# power_board.net
KiCad netlist of a schematic drawn in EAGLE
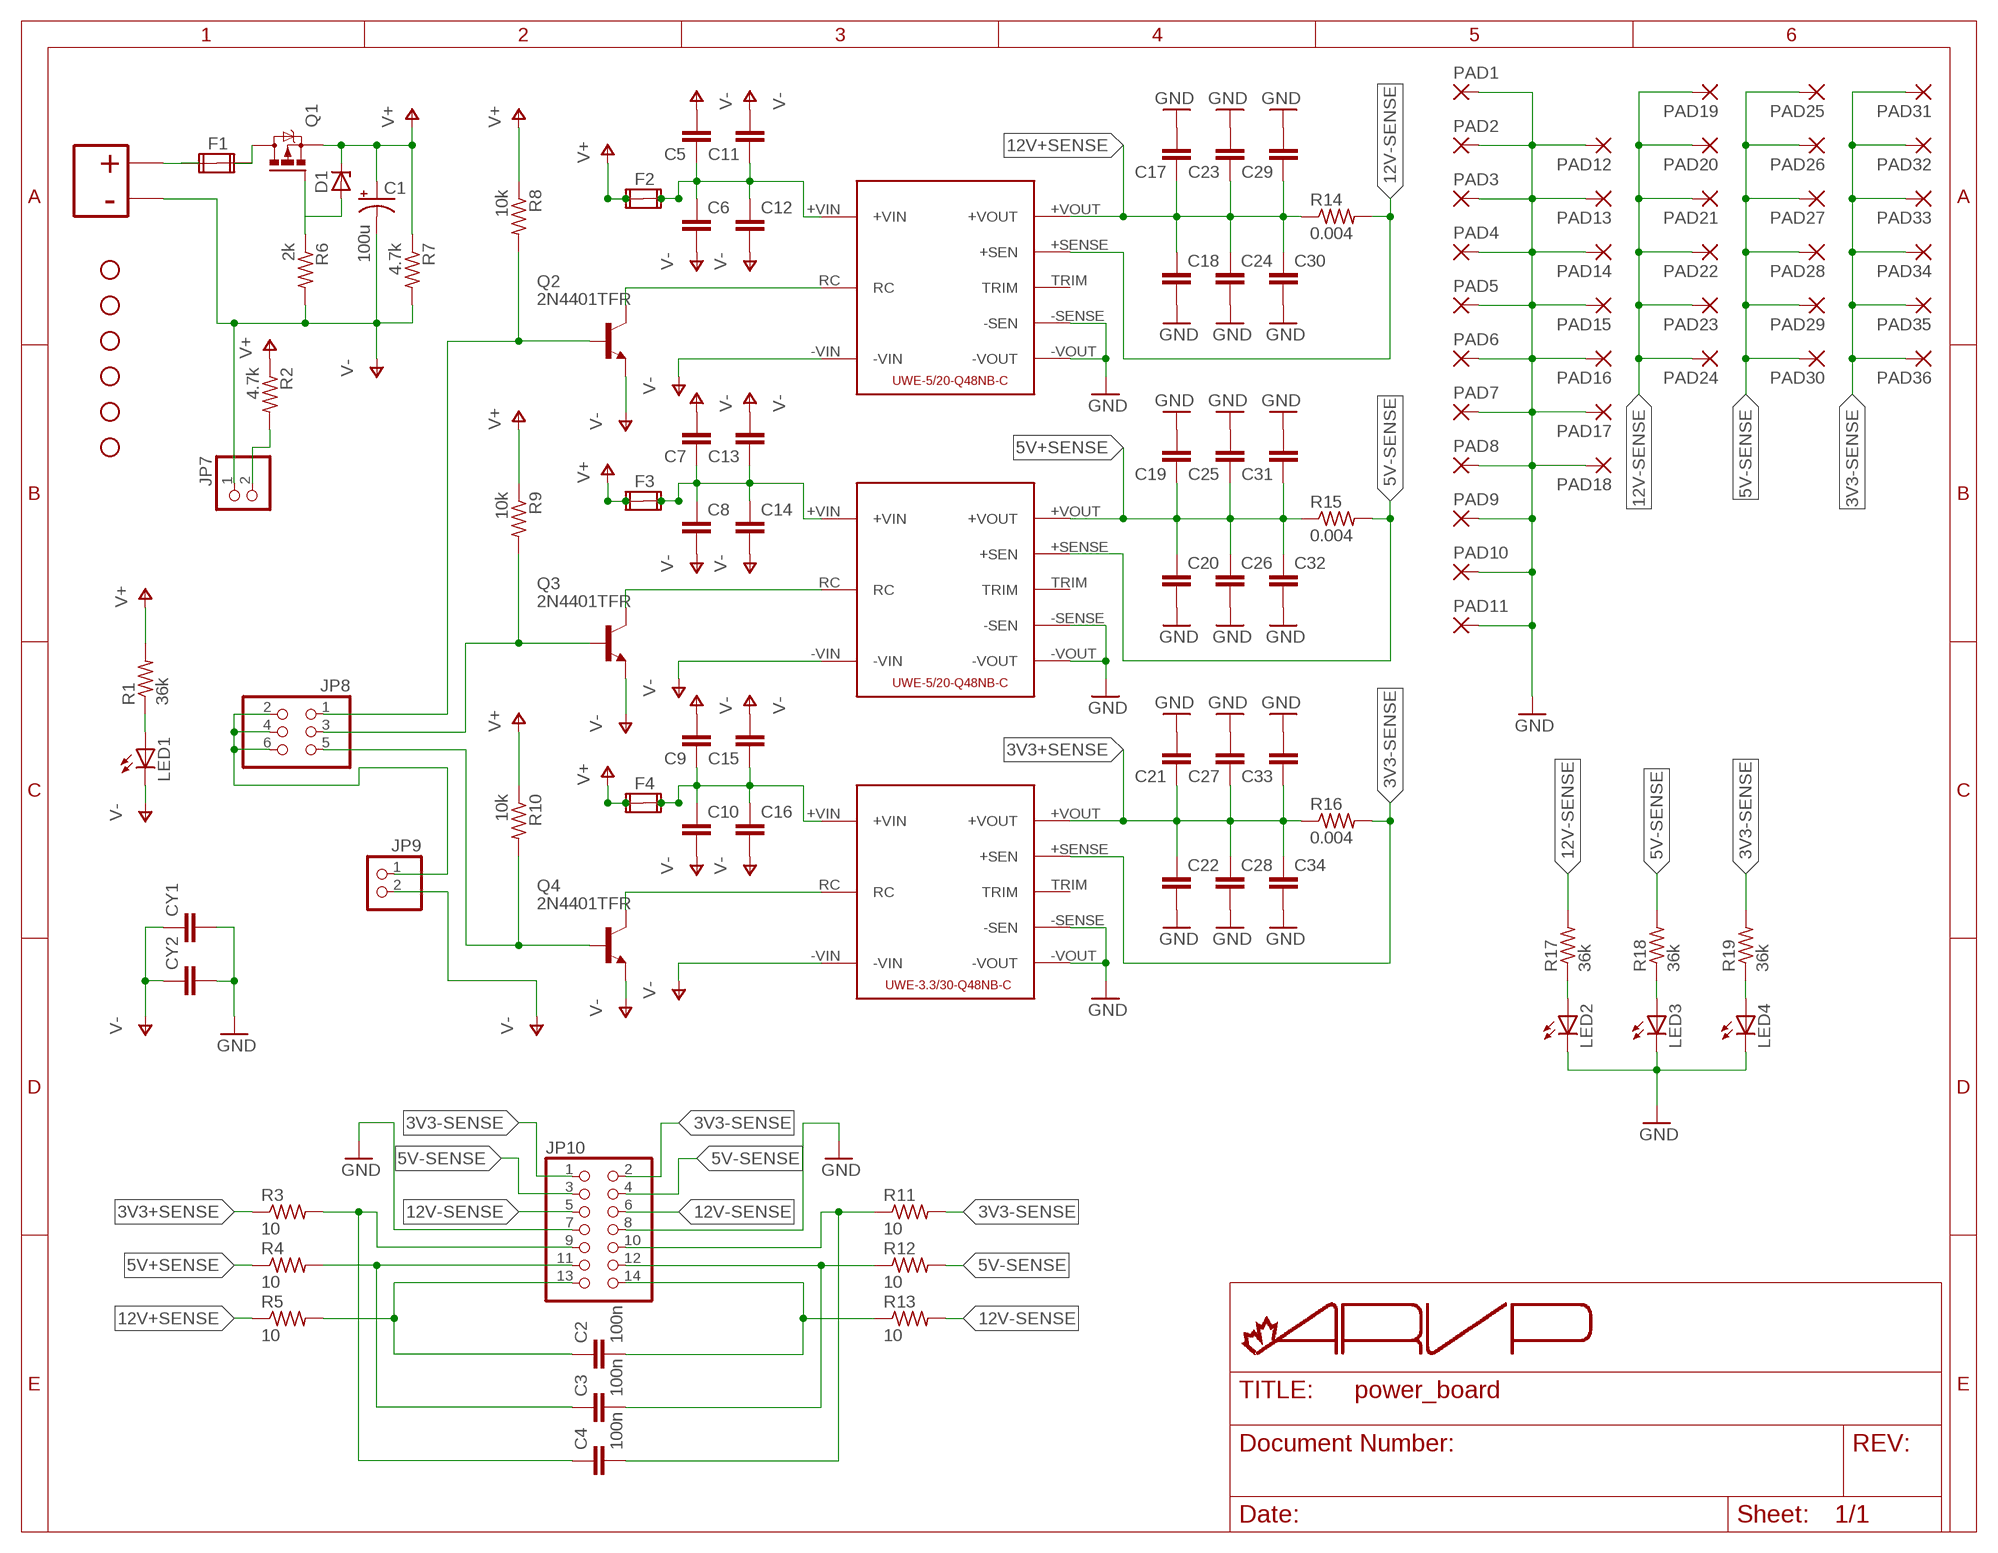
[diagram p0: schematic, sheet 1]

(export (version "E")
  (design (tool "Eeschema 10.0.6"))
  (components
    (comp (ref "C1")
      (value "100u")
      (footprint "eagle-import:E3,5-8")
      (libsource (lib "eagle-import") (part "CPOL-USE3.5-8"))
    )
    (comp (ref "C2")
      (value "100n")
      (footprint "eagle-import:C025-024X044")
      (libsource (lib "eagle-import") (part "C-EU025-024X044"))
    )
    (comp (ref "C3")
      (value "100n")
      (footprint "eagle-import:C025-024X044")
      (libsource (lib "eagle-import") (part "C-EU025-024X044"))
    )
    (comp (ref "C4")
      (value "100n")
      (footprint "eagle-import:C025-024X044")
      (libsource (lib "eagle-import") (part "C-EU025-024X044"))
    )
    (comp (ref "C5")
      (value "C-EU050-035X075")
      (footprint "eagle-import:C050-035X075")
      (libsource (lib "eagle-import") (part "C-EU050-035X075"))
    )
    (comp (ref "C6")
      (value "C-EU050-035X075")
      (footprint "eagle-import:C050-035X075")
      (libsource (lib "eagle-import") (part "C-EU050-035X075"))
    )
    (comp (ref "C7")
      (value "C-EU050-035X075")
      (footprint "eagle-import:C050-035X075")
      (libsource (lib "eagle-import") (part "C-EU050-035X075"))
    )
    (comp (ref "C8")
      (value "C-EU050-035X075")
      (footprint "eagle-import:C050-035X075")
      (libsource (lib "eagle-import") (part "C-EU050-035X075"))
    )
    (comp (ref "C9")
      (value "C-EU050-035X075")
      (footprint "eagle-import:C050-035X075")
      (libsource (lib "eagle-import") (part "C-EU050-035X075"))
    )
    (comp (ref "C10")
      (value "C-EU050-035X075")
      (footprint "eagle-import:C050-035X075")
      (libsource (lib "eagle-import") (part "C-EU050-035X075"))
    )
    (comp (ref "C11")
      (value "C-EU050-035X075")
      (footprint "eagle-import:C050-035X075")
      (libsource (lib "eagle-import") (part "C-EU050-035X075"))
    )
    (comp (ref "C12")
      (value "C-EU050-035X075")
      (footprint "eagle-import:C050-035X075")
      (libsource (lib "eagle-import") (part "C-EU050-035X075"))
    )
    (comp (ref "C13")
      (value "C-EU050-035X075")
      (footprint "eagle-import:C050-035X075")
      (libsource (lib "eagle-import") (part "C-EU050-035X075"))
    )
    (comp (ref "C14")
      (value "C-EU050-035X075")
      (footprint "eagle-import:C050-035X075")
      (libsource (lib "eagle-import") (part "C-EU050-035X075"))
    )
    (comp (ref "C15")
      (value "C-EU050-035X075")
      (footprint "eagle-import:C050-035X075")
      (libsource (lib "eagle-import") (part "C-EU050-035X075"))
    )
    (comp (ref "C16")
      (value "C-EU050-035X075")
      (footprint "eagle-import:C050-035X075")
      (libsource (lib "eagle-import") (part "C-EU050-035X075"))
    )
    (comp (ref "C17")
      (value "C-EU025-040X050")
      (footprint "eagle-import:C025-040X050")
      (libsource (lib "eagle-import") (part "C-EU025-040X050"))
    )
    (comp (ref "C18")
      (value "C-EU025-040X050")
      (footprint "eagle-import:C025-040X050")
      (libsource (lib "eagle-import") (part "C-EU025-040X050"))
    )
    (comp (ref "C19")
      (value "C-EU025-040X050")
      (footprint "eagle-import:C025-040X050")
      (libsource (lib "eagle-import") (part "C-EU025-040X050"))
    )
    (comp (ref "C20")
      (value "C-EU025-040X050")
      (footprint "eagle-import:C025-040X050")
      (libsource (lib "eagle-import") (part "C-EU025-040X050"))
    )
    (comp (ref "C21")
      (value "C-EU025-040X050")
      (footprint "eagle-import:C025-040X050")
      (libsource (lib "eagle-import") (part "C-EU025-040X050"))
    )
    (comp (ref "C22")
      (value "C-EU025-040X050")
      (footprint "eagle-import:C025-040X050")
      (libsource (lib "eagle-import") (part "C-EU025-040X050"))
    )
    (comp (ref "C23")
      (value "C-EU025-040X050")
      (footprint "eagle-import:C025-040X050")
      (libsource (lib "eagle-import") (part "C-EU025-040X050"))
    )
    (comp (ref "C24")
      (value "C-EU025-040X050")
      (footprint "eagle-import:C025-040X050")
      (libsource (lib "eagle-import") (part "C-EU025-040X050"))
    )
    (comp (ref "C25")
      (value "C-EU025-040X050")
      (footprint "eagle-import:C025-040X050")
      (libsource (lib "eagle-import") (part "C-EU025-040X050"))
    )
    (comp (ref "C26")
      (value "C-EU025-040X050")
      (footprint "eagle-import:C025-040X050")
      (libsource (lib "eagle-import") (part "C-EU025-040X050"))
    )
    (comp (ref "C27")
      (value "C-EU025-040X050")
      (footprint "eagle-import:C025-040X050")
      (libsource (lib "eagle-import") (part "C-EU025-040X050"))
    )
    (comp (ref "C28")
      (value "C-EU025-040X050")
      (footprint "eagle-import:C025-040X050")
      (libsource (lib "eagle-import") (part "C-EU025-040X050"))
    )
    (comp (ref "C29")
      (value "C-EU025-040X050")
      (footprint "eagle-import:C025-040X050")
      (libsource (lib "eagle-import") (part "C-EU025-040X050"))
    )
    (comp (ref "C30")
      (value "C-EU025-040X050")
      (footprint "eagle-import:C025-040X050")
      (libsource (lib "eagle-import") (part "C-EU025-040X050"))
    )
    (comp (ref "C31")
      (value "C-EU025-040X050")
      (footprint "eagle-import:C025-040X050")
      (libsource (lib "eagle-import") (part "C-EU025-040X050"))
    )
    (comp (ref "C32")
      (value "C-EU025-040X050")
      (footprint "eagle-import:C025-040X050")
      (libsource (lib "eagle-import") (part "C-EU025-040X050"))
    )
    (comp (ref "C33")
      (value "C-EU025-040X050")
      (footprint "eagle-import:C025-040X050")
      (libsource (lib "eagle-import") (part "C-EU025-040X050"))
    )
    (comp (ref "C34")
      (value "C-EU025-040X050")
      (footprint "eagle-import:C025-040X050")
      (libsource (lib "eagle-import") (part "C-EU025-040X050"))
    )
    (comp (ref "CY1")
      (value "CYYC7B5")
      (footprint "eagle-import:YC7B5")
      (libsource (lib "eagle-import") (part "CYYC7B5"))
    )
    (comp (ref "CY2")
      (value "CYYC7B5")
      (footprint "eagle-import:YC7B5")
      (libsource (lib "eagle-import") (part "CYYC7B5"))
    )
    (comp (ref "D1")
      (value "BZV10")
      (footprint "eagle-import:DO34Z7")
      (libsource (lib "eagle-import") (part "BZV10"))
    )
    (comp (ref "F1")
      (value "FUSE2P")
      (footprint "eagle-import:FUSE1")
      (libsource (lib "eagle-import") (part "FUSE2P"))
    )
    (comp (ref "F2")
      (value "FUSE2P")
      (footprint "eagle-import:FUSE1")
      (libsource (lib "eagle-import") (part "FUSE2P"))
    )
    (comp (ref "F3")
      (value "FUSE2P")
      (footprint "eagle-import:FUSE1")
      (libsource (lib "eagle-import") (part "FUSE2P"))
    )
    (comp (ref "F4")
      (value "FUSE2P")
      (footprint "eagle-import:FUSE1")
      (libsource (lib "eagle-import") (part "FUSE2P"))
    )
    (comp (ref "JP1")
      (value "STAND-OFF")
      (footprint "eagle-import:STAND-OFF")
      (libsource (lib "eagle-import") (part "STAND-OFF"))
    )
    (comp (ref "JP2")
      (value "STAND-OFF")
      (footprint "eagle-import:STAND-OFF")
      (libsource (lib "eagle-import") (part "STAND-OFF"))
    )
    (comp (ref "JP3")
      (value "STAND-OFF")
      (footprint "eagle-import:STAND-OFF")
      (libsource (lib "eagle-import") (part "STAND-OFF"))
    )
    (comp (ref "JP4")
      (value "STAND-OFF")
      (footprint "eagle-import:STAND-OFF")
      (libsource (lib "eagle-import") (part "STAND-OFF"))
    )
    (comp (ref "JP5")
      (value "STAND-OFF")
      (footprint "eagle-import:STAND-OFF")
      (libsource (lib "eagle-import") (part "STAND-OFF"))
    )
    (comp (ref "JP6")
      (value "STAND-OFF")
      (footprint "eagle-import:STAND-OFF")
      (libsource (lib "eagle-import") (part "STAND-OFF"))
    )
    (comp (ref "JP7")
      (value "PINHD-1X2/90")
      (footprint "eagle-import:1X02_90")
      (libsource (lib "eagle-import") (part "PINHD-1X2/90"))
    )
    (comp (ref "JP8")
      (value "PINHD-2X3/90")
      (footprint "eagle-import:2X03_90")
      (libsource (lib "eagle-import") (part "PINHD-2X3/90"))
    )
    (comp (ref "JP9")
      (value "PINHD-1X2/90")
      (footprint "eagle-import:1X02_90")
      (libsource (lib "eagle-import") (part "PINHD-1X2/90"))
    )
    (comp (ref "JP10")
      (value "PINHD-2X7")
      (footprint "eagle-import:2X07")
      (libsource (lib "eagle-import") (part "PINHD-2X7"))
    )
    (comp (ref "LED1")
      (value "LED3MM")
      (footprint "eagle-import:LED3MM")
      (libsource (lib "eagle-import") (part "LED3MM"))
    )
    (comp (ref "LED2")
      (value "LED3MM")
      (footprint "eagle-import:LED3MM")
      (libsource (lib "eagle-import") (part "LED3MM"))
    )
    (comp (ref "LED3")
      (value "LED3MM")
      (footprint "eagle-import:LED3MM")
      (libsource (lib "eagle-import") (part "LED3MM"))
    )
    (comp (ref "LED4")
      (value "LED3MM")
      (footprint "eagle-import:LED3MM")
      (libsource (lib "eagle-import") (part "LED3MM"))
    )
    (comp (ref "PAD1")
      (value "WIREPAD3,17/1,3")
      (footprint "eagle-import:3,17_1,3")
      (libsource (lib "eagle-import") (part "WIREPAD3,17/1,3"))
    )
    (comp (ref "PAD2")
      (value "WIREPAD3,17/1,3")
      (footprint "eagle-import:3,17_1,3")
      (libsource (lib "eagle-import") (part "WIREPAD3,17/1,3"))
    )
    (comp (ref "PAD3")
      (value "WIREPAD3,17/1,3")
      (footprint "eagle-import:3,17_1,3")
      (libsource (lib "eagle-import") (part "WIREPAD3,17/1,3"))
    )
    (comp (ref "PAD4")
      (value "WIREPAD3,17/1,3")
      (footprint "eagle-import:3,17_1,3")
      (libsource (lib "eagle-import") (part "WIREPAD3,17/1,3"))
    )
    (comp (ref "PAD5")
      (value "WIREPAD3,17/1,3")
      (footprint "eagle-import:3,17_1,3")
      (libsource (lib "eagle-import") (part "WIREPAD3,17/1,3"))
    )
    (comp (ref "PAD6")
      (value "WIREPAD3,17/1,3")
      (footprint "eagle-import:3,17_1,3")
      (libsource (lib "eagle-import") (part "WIREPAD3,17/1,3"))
    )
    (comp (ref "PAD7")
      (value "WIREPAD3,17/1,3")
      (footprint "eagle-import:3,17_1,3")
      (libsource (lib "eagle-import") (part "WIREPAD3,17/1,3"))
    )
    (comp (ref "PAD8")
      (value "WIREPAD3,17/1,3")
      (footprint "eagle-import:3,17_1,3")
      (libsource (lib "eagle-import") (part "WIREPAD3,17/1,3"))
    )
    (comp (ref "PAD9")
      (value "WIREPAD3,17/1,3")
      (footprint "eagle-import:3,17_1,3")
      (libsource (lib "eagle-import") (part "WIREPAD3,17/1,3"))
    )
    (comp (ref "PAD10")
      (value "WIREPAD3,17/1,3")
      (footprint "eagle-import:3,17_1,3")
      (libsource (lib "eagle-import") (part "WIREPAD3,17/1,3"))
    )
    (comp (ref "PAD11")
      (value "WIREPAD3,17/1,3")
      (footprint "eagle-import:3,17_1,3")
      (libsource (lib "eagle-import") (part "WIREPAD3,17/1,3"))
    )
    (comp (ref "PAD12")
      (value "WIREPAD3,17/1,3")
      (footprint "eagle-import:3,17_1,3")
      (libsource (lib "eagle-import") (part "WIREPAD3,17/1,3"))
    )
    (comp (ref "PAD13")
      (value "WIREPAD3,17/1,3")
      (footprint "eagle-import:3,17_1,3")
      (libsource (lib "eagle-import") (part "WIREPAD3,17/1,3"))
    )
    (comp (ref "PAD14")
      (value "WIREPAD3,17/1,3")
      (footprint "eagle-import:3,17_1,3")
      (libsource (lib "eagle-import") (part "WIREPAD3,17/1,3"))
    )
    (comp (ref "PAD15")
      (value "WIREPAD3,17/1,3")
      (footprint "eagle-import:3,17_1,3")
      (libsource (lib "eagle-import") (part "WIREPAD3,17/1,3"))
    )
    (comp (ref "PAD16")
      (value "WIREPAD3,17/1,3")
      (footprint "eagle-import:3,17_1,3")
      (libsource (lib "eagle-import") (part "WIREPAD3,17/1,3"))
    )
    (comp (ref "PAD17")
      (value "WIREPAD3,17/1,3")
      (footprint "eagle-import:3,17_1,3")
      (libsource (lib "eagle-import") (part "WIREPAD3,17/1,3"))
    )
    (comp (ref "PAD18")
      (value "WIREPAD3,17/1,3")
      (footprint "eagle-import:3,17_1,3")
      (libsource (lib "eagle-import") (part "WIREPAD3,17/1,3"))
    )
    (comp (ref "PAD19")
      (value "WIREPAD3,17/1,3")
      (footprint "eagle-import:3,17_1,3")
      (libsource (lib "eagle-import") (part "WIREPAD3,17/1,3"))
    )
    (comp (ref "PAD20")
      (value "WIREPAD3,17/1,3")
      (footprint "eagle-import:3,17_1,3")
      (libsource (lib "eagle-import") (part "WIREPAD3,17/1,3"))
    )
    (comp (ref "PAD21")
      (value "WIREPAD3,17/1,3")
      (footprint "eagle-import:3,17_1,3")
      (libsource (lib "eagle-import") (part "WIREPAD3,17/1,3"))
    )
    (comp (ref "PAD22")
      (value "WIREPAD3,17/1,3")
      (footprint "eagle-import:3,17_1,3")
      (libsource (lib "eagle-import") (part "WIREPAD3,17/1,3"))
    )
    (comp (ref "PAD23")
      (value "WIREPAD3,17/1,3")
      (footprint "eagle-import:3,17_1,3")
      (libsource (lib "eagle-import") (part "WIREPAD3,17/1,3"))
    )
    (comp (ref "PAD24")
      (value "WIREPAD3,17/1,3")
      (footprint "eagle-import:3,17_1,3")
      (libsource (lib "eagle-import") (part "WIREPAD3,17/1,3"))
    )
    (comp (ref "PAD25")
      (value "WIREPAD3,17/1,3")
      (footprint "eagle-import:3,17_1,3")
      (libsource (lib "eagle-import") (part "WIREPAD3,17/1,3"))
    )
    (comp (ref "PAD26")
      (value "WIREPAD3,17/1,3")
      (footprint "eagle-import:3,17_1,3")
      (libsource (lib "eagle-import") (part "WIREPAD3,17/1,3"))
    )
    (comp (ref "PAD27")
      (value "WIREPAD3,17/1,3")
      (footprint "eagle-import:3,17_1,3")
      (libsource (lib "eagle-import") (part "WIREPAD3,17/1,3"))
    )
    (comp (ref "PAD28")
      (value "WIREPAD3,17/1,3")
      (footprint "eagle-import:3,17_1,3")
      (libsource (lib "eagle-import") (part "WIREPAD3,17/1,3"))
    )
    (comp (ref "PAD29")
      (value "WIREPAD3,17/1,3")
      (footprint "eagle-import:3,17_1,3")
      (libsource (lib "eagle-import") (part "WIREPAD3,17/1,3"))
    )
    (comp (ref "PAD30")
      (value "WIREPAD3,17/1,3")
      (footprint "eagle-import:3,17_1,3")
      (libsource (lib "eagle-import") (part "WIREPAD3,17/1,3"))
    )
    (comp (ref "PAD31")
      (value "WIREPAD3,17/1,3")
      (footprint "eagle-import:3,17_1,3")
      (libsource (lib "eagle-import") (part "WIREPAD3,17/1,3"))
    )
    (comp (ref "PAD32")
      (value "WIREPAD3,17/1,3")
      (footprint "eagle-import:3,17_1,3")
      (libsource (lib "eagle-import") (part "WIREPAD3,17/1,3"))
    )
    (comp (ref "PAD33")
      (value "WIREPAD3,17/1,3")
      (footprint "eagle-import:3,17_1,3")
      (libsource (lib "eagle-import") (part "WIREPAD3,17/1,3"))
    )
    (comp (ref "PAD34")
      (value "WIREPAD3,17/1,3")
      (footprint "eagle-import:3,17_1,3")
      (libsource (lib "eagle-import") (part "WIREPAD3,17/1,3"))
    )
    (comp (ref "PAD35")
      (value "WIREPAD3,17/1,3")
      (footprint "eagle-import:3,17_1,3")
      (libsource (lib "eagle-import") (part "WIREPAD3,17/1,3"))
    )
    (comp (ref "PAD36")
      (value "WIREPAD3,17/1,3")
      (footprint "eagle-import:3,17_1,3")
      (libsource (lib "eagle-import") (part "WIREPAD3,17/1,3"))
    )
    (comp (ref "Q1")
      (value "IPP80P03P4L04AKSA1")
      (footprint "eagle-import:TO220BV")
      (libsource (lib "eagle-import") (part "IPP80P03P4L04AKSA1"))
    )
    (comp (ref "Q2")
      (value "2N4401TFR")
      (footprint "eagle-import:TO92-EBC")
      (libsource (lib "eagle-import") (part "2N4401TFR"))
    )
    (comp (ref "Q3")
      (value "2N4401TFR")
      (footprint "eagle-import:TO92-EBC")
      (libsource (lib "eagle-import") (part "2N4401TFR"))
    )
    (comp (ref "Q4")
      (value "2N4401TFR")
      (footprint "eagle-import:TO92-EBC")
      (libsource (lib "eagle-import") (part "2N4401TFR"))
    )
    (comp (ref "R1")
      (value "36k")
      (footprint "eagle-import:0204_7")
      (libsource (lib "eagle-import") (part "resistor_R-US_0204/7"))
    )
    (comp (ref "R2")
      (value "4.7k")
      (footprint "eagle-import:0204_7")
      (libsource (lib "eagle-import") (part "resistor_R-US_0204/7"))
    )
    (comp (ref "R3")
      (value "10")
      (footprint "eagle-import:0204_5")
      (libsource (lib "eagle-import") (part "R-US_0204/5"))
    )
    (comp (ref "R4")
      (value "10")
      (footprint "eagle-import:0204_5")
      (libsource (lib "eagle-import") (part "R-US_0204/5"))
    )
    (comp (ref "R5")
      (value "10")
      (footprint "eagle-import:0204_5")
      (libsource (lib "eagle-import") (part "R-US_0204/5"))
    )
    (comp (ref "R6")
      (value "2k")
      (footprint "eagle-import:0204_7")
      (libsource (lib "eagle-import") (part "resistor_R-US_0204/7"))
    )
    (comp (ref "R7")
      (value "4.7k")
      (footprint "eagle-import:0204_7")
      (libsource (lib "eagle-import") (part "resistor_R-US_0204/7"))
    )
    (comp (ref "R8")
      (value "10k")
      (footprint "eagle-import:0204_7")
      (libsource (lib "eagle-import") (part "resistor_R-US_0204/7"))
    )
    (comp (ref "R9")
      (value "10k")
      (footprint "eagle-import:0204_7")
      (libsource (lib "eagle-import") (part "resistor_R-US_0204/7"))
    )
    (comp (ref "R10")
      (value "10k")
      (footprint "eagle-import:0204_7")
      (libsource (lib "eagle-import") (part "resistor_R-US_0204/7"))
    )
    (comp (ref "R11")
      (value "10")
      (footprint "eagle-import:0204_5")
      (libsource (lib "eagle-import") (part "R-US_0204/5"))
    )
    (comp (ref "R12")
      (value "10")
      (footprint "eagle-import:0204_5")
      (libsource (lib "eagle-import") (part "R-US_0204/5"))
    )
    (comp (ref "R13")
      (value "10")
      (footprint "eagle-import:0204_5")
      (libsource (lib "eagle-import") (part "R-US_0204/5"))
    )
    (comp (ref "R14")
      (value "0.004")
      (footprint "eagle-import:0617_22")
      (libsource (lib "eagle-import") (part "R-US_0617/22"))
    )
    (comp (ref "R15")
      (value "0.004")
      (footprint "eagle-import:0617_22")
      (libsource (lib "eagle-import") (part "R-US_0617/22"))
    )
    (comp (ref "R16")
      (value "0.004")
      (footprint "eagle-import:0617_22")
      (libsource (lib "eagle-import") (part "R-US_0617/22"))
    )
    (comp (ref "R17")
      (value "36k")
      (footprint "eagle-import:0204_7")
      (libsource (lib "eagle-import") (part "resistor_R-US_0204/7"))
    )
    (comp (ref "R18")
      (value "36k")
      (footprint "eagle-import:0204_7")
      (libsource (lib "eagle-import") (part "resistor_R-US_0204/7"))
    )
    (comp (ref "R19")
      (value "36k")
      (footprint "eagle-import:0204_7")
      (libsource (lib "eagle-import") (part "resistor_R-US_0204/7"))
    )
    (comp (ref "T1")
      (value "2_POS_TERMINAL")
      (footprint "eagle-import:PHOENIX_CONTACT_MKDS_5_2-7.62")
      (libsource (lib "eagle-import") (part "2_POS_TERMINAL"))
    )
    (comp (ref "U1")
      (value "UWE-5/20-Q48NB-C")
      (footprint "eagle-import:UWE-100-120W")
      (libsource (lib "eagle-import") (part "UWE-5/20-Q48NB-C"))
    )
    (comp (ref "U2")
      (value "UWE-3.3/30-Q48NB-C")
      (footprint "eagle-import:UWE-100-120W")
      (libsource (lib "eagle-import") (part "UWE-3.3/30-Q48NB-C"))
    )
    (comp (ref "U4")
      (value "UWE-12/10-Q48NB-C")
      (footprint "eagle-import:UWE-100-120W")
      (libsource (lib "eagle-import") (part "UWE-12/10-Q48NB-C"))
    )
  )
  (nets
    (net (code "1") (name "3V3+SENSE") (class "Default")
      (node (ref "C21") (pin "1") (pinfunction "1_1") (pintype "passive"))
      (node (ref "C22") (pin "1") (pinfunction "1_1") (pintype "passive"))
      (node (ref "C27") (pin "1") (pinfunction "1_1") (pintype "passive"))
      (node (ref "C28") (pin "1") (pinfunction "1_1") (pintype "passive"))
      (node (ref "C33") (pin "1") (pinfunction "1_1") (pintype "passive"))
      (node (ref "C34") (pin "1") (pinfunction "1_1") (pintype "passive"))
      (node (ref "R16") (pin "1") (pinfunction "1_1") (pintype "passive"))
      (node (ref "R3") (pin "1") (pinfunction "1_1") (pintype "passive"))
      (node (ref "U2") (pin "+VOUT") (pinfunction "+VOUT_+VOUT") (pintype "power_in"))
    )
    (net (code "2") (name "3V3-SENSE") (class "Default")
      (node (ref "JP10") (pin "1") (pinfunction "1_1") (pintype "passive"))
      (node (ref "JP10") (pin "2") (pinfunction "2_2") (pintype "passive"))
      (node (ref "PAD31") (pin "1") (pinfunction "P_1") (pintype "passive"))
      (node (ref "PAD32") (pin "1") (pinfunction "P_1") (pintype "passive"))
      (node (ref "PAD33") (pin "1") (pinfunction "P_1") (pintype "passive"))
      (node (ref "PAD34") (pin "1") (pinfunction "P_1") (pintype "passive"))
      (node (ref "PAD35") (pin "1") (pinfunction "P_1") (pintype "passive"))
      (node (ref "PAD36") (pin "1") (pinfunction "P_1") (pintype "passive"))
      (node (ref "R11") (pin "2") (pinfunction "2_2") (pintype "passive"))
      (node (ref "R16") (pin "2") (pinfunction "2_2") (pintype "passive"))
      (node (ref "R19") (pin "2") (pinfunction "2_2") (pintype "passive"))
      (node (ref "U2") (pin "+SENSE") (pinfunction "+SEN_+SENSE") (pintype "bidirectional"))
    )
    (net (code "3") (name "5V+SENSE") (class "Default")
      (node (ref "C19") (pin "1") (pinfunction "1_1") (pintype "passive"))
      (node (ref "C20") (pin "1") (pinfunction "1_1") (pintype "passive"))
      (node (ref "C25") (pin "1") (pinfunction "1_1") (pintype "passive"))
      (node (ref "C26") (pin "1") (pinfunction "1_1") (pintype "passive"))
      (node (ref "C31") (pin "1") (pinfunction "1_1") (pintype "passive"))
      (node (ref "C32") (pin "1") (pinfunction "1_1") (pintype "passive"))
      (node (ref "R15") (pin "1") (pinfunction "1_1") (pintype "passive"))
      (node (ref "R4") (pin "1") (pinfunction "1_1") (pintype "passive"))
      (node (ref "U1") (pin "+VOUT") (pinfunction "+VOUT_+VOUT") (pintype "power_in"))
    )
    (net (code "4") (name "5V-SENSE") (class "Default")
      (node (ref "JP10") (pin "3") (pinfunction "3_3") (pintype "passive"))
      (node (ref "JP10") (pin "4") (pinfunction "4_4") (pintype "passive"))
      (node (ref "PAD25") (pin "1") (pinfunction "P_1") (pintype "passive"))
      (node (ref "PAD26") (pin "1") (pinfunction "P_1") (pintype "passive"))
      (node (ref "PAD27") (pin "1") (pinfunction "P_1") (pintype "passive"))
      (node (ref "PAD28") (pin "1") (pinfunction "P_1") (pintype "passive"))
      (node (ref "PAD29") (pin "1") (pinfunction "P_1") (pintype "passive"))
      (node (ref "PAD30") (pin "1") (pinfunction "P_1") (pintype "passive"))
      (node (ref "R12") (pin "2") (pinfunction "2_2") (pintype "passive"))
      (node (ref "R15") (pin "2") (pinfunction "2_2") (pintype "passive"))
      (node (ref "R18") (pin "2") (pinfunction "2_2") (pintype "passive"))
      (node (ref "U1") (pin "+SENSE") (pinfunction "+SEN_+SENSE") (pintype "bidirectional"))
    )
    (net (code "5") (name "12V+SENSE") (class "Default")
      (node (ref "C17") (pin "1") (pinfunction "1_1") (pintype "passive"))
      (node (ref "C18") (pin "1") (pinfunction "1_1") (pintype "passive"))
      (node (ref "C23") (pin "1") (pinfunction "1_1") (pintype "passive"))
      (node (ref "C24") (pin "1") (pinfunction "1_1") (pintype "passive"))
      (node (ref "C29") (pin "1") (pinfunction "1_1") (pintype "passive"))
      (node (ref "C30") (pin "1") (pinfunction "1_1") (pintype "passive"))
      (node (ref "R14") (pin "1") (pinfunction "1_1") (pintype "passive"))
      (node (ref "R5") (pin "1") (pinfunction "1_1") (pintype "passive"))
      (node (ref "U4") (pin "+VOUT") (pinfunction "+VOUT_+VOUT") (pintype "power_in"))
    )
    (net (code "6") (name "12V-SENSE") (class "Default")
      (node (ref "JP10") (pin "5") (pinfunction "5_5") (pintype "passive"))
      (node (ref "JP10") (pin "6") (pinfunction "6_6") (pintype "passive"))
      (node (ref "PAD19") (pin "1") (pinfunction "P_1") (pintype "passive"))
      (node (ref "PAD20") (pin "1") (pinfunction "P_1") (pintype "passive"))
      (node (ref "PAD21") (pin "1") (pinfunction "P_1") (pintype "passive"))
      (node (ref "PAD22") (pin "1") (pinfunction "P_1") (pintype "passive"))
      (node (ref "PAD23") (pin "1") (pinfunction "P_1") (pintype "passive"))
      (node (ref "PAD24") (pin "1") (pinfunction "P_1") (pintype "passive"))
      (node (ref "R13") (pin "2") (pinfunction "2_2") (pintype "passive"))
      (node (ref "R14") (pin "2") (pinfunction "2_2") (pintype "passive"))
      (node (ref "R17") (pin "2") (pinfunction "2_2") (pintype "passive"))
      (node (ref "U4") (pin "+SENSE") (pinfunction "+SEN_+SENSE") (pintype "bidirectional"))
    )
    (net (code "7") (name "GND") (class "Default")
      (node (ref "C17") (pin "2") (pinfunction "2_2") (pintype "passive"))
      (node (ref "C18") (pin "2") (pinfunction "2_2") (pintype "passive"))
      (node (ref "C19") (pin "2") (pinfunction "2_2") (pintype "passive"))
      (node (ref "C20") (pin "2") (pinfunction "2_2") (pintype "passive"))
      (node (ref "C21") (pin "2") (pinfunction "2_2") (pintype "passive"))
      (node (ref "C22") (pin "2") (pinfunction "2_2") (pintype "passive"))
      (node (ref "C23") (pin "2") (pinfunction "2_2") (pintype "passive"))
      (node (ref "C24") (pin "2") (pinfunction "2_2") (pintype "passive"))
      (node (ref "C25") (pin "2") (pinfunction "2_2") (pintype "passive"))
      (node (ref "C26") (pin "2") (pinfunction "2_2") (pintype "passive"))
      (node (ref "C27") (pin "2") (pinfunction "2_2") (pintype "passive"))
      (node (ref "C28") (pin "2") (pinfunction "2_2") (pintype "passive"))
      (node (ref "C29") (pin "2") (pinfunction "2_2") (pintype "passive"))
      (node (ref "C30") (pin "2") (pinfunction "2_2") (pintype "passive"))
      (node (ref "C31") (pin "2") (pinfunction "2_2") (pintype "passive"))
      (node (ref "C32") (pin "2") (pinfunction "2_2") (pintype "passive"))
      (node (ref "C33") (pin "2") (pinfunction "2_2") (pintype "passive"))
      (node (ref "C34") (pin "2") (pinfunction "2_2") (pintype "passive"))
      (node (ref "CY1") (pin "2") (pinfunction "2_2") (pintype "passive"))
      (node (ref "CY2") (pin "2") (pinfunction "2_2") (pintype "passive"))
      (node (ref "JP10") (pin "7") (pinfunction "7_7") (pintype "passive"))
      (node (ref "JP10") (pin "8") (pinfunction "8_8") (pintype "passive"))
      (node (ref "LED2") (pin "K") (pinfunction "C_K") (pintype "passive"))
      (node (ref "LED3") (pin "K") (pinfunction "C_K") (pintype "passive"))
      (node (ref "LED4") (pin "K") (pinfunction "C_K") (pintype "passive"))
      (node (ref "PAD1") (pin "1") (pinfunction "P_1") (pintype "passive"))
      (node (ref "PAD10") (pin "1") (pinfunction "P_1") (pintype "passive"))
      (node (ref "PAD11") (pin "1") (pinfunction "P_1") (pintype "passive"))
      (node (ref "PAD12") (pin "1") (pinfunction "P_1") (pintype "passive"))
      (node (ref "PAD13") (pin "1") (pinfunction "P_1") (pintype "passive"))
      (node (ref "PAD14") (pin "1") (pinfunction "P_1") (pintype "passive"))
      (node (ref "PAD15") (pin "1") (pinfunction "P_1") (pintype "passive"))
      (node (ref "PAD16") (pin "1") (pinfunction "P_1") (pintype "passive"))
      (node (ref "PAD17") (pin "1") (pinfunction "P_1") (pintype "passive"))
      (node (ref "PAD18") (pin "1") (pinfunction "P_1") (pintype "passive"))
      (node (ref "PAD2") (pin "1") (pinfunction "P_1") (pintype "passive"))
      (node (ref "PAD3") (pin "1") (pinfunction "P_1") (pintype "passive"))
      (node (ref "PAD4") (pin "1") (pinfunction "P_1") (pintype "passive"))
      (node (ref "PAD5") (pin "1") (pinfunction "P_1") (pintype "passive"))
      (node (ref "PAD6") (pin "1") (pinfunction "P_1") (pintype "passive"))
      (node (ref "PAD7") (pin "1") (pinfunction "P_1") (pintype "passive"))
      (node (ref "PAD8") (pin "1") (pinfunction "P_1") (pintype "passive"))
      (node (ref "PAD9") (pin "1") (pinfunction "P_1") (pintype "passive"))
      (node (ref "U1") (pin "-SENSE") (pinfunction "-SEN_-SENSE") (pintype "bidirectional"))
      (node (ref "U1") (pin "-VOUT") (pinfunction "-VOUT_-VOUT") (pintype "power_in"))
      (node (ref "U2") (pin "-SENSE") (pinfunction "-SEN_-SENSE") (pintype "bidirectional"))
      (node (ref "U2") (pin "-VOUT") (pinfunction "-VOUT_-VOUT") (pintype "power_in"))
      (node (ref "U4") (pin "-SENSE") (pinfunction "-SEN_-SENSE") (pintype "bidirectional"))
      (node (ref "U4") (pin "-VOUT") (pinfunction "-VOUT_-VOUT") (pintype "power_in"))
    )
    (net (code "8") (name "Net-(C2-Pad1)") (class "Default")
      (node (ref "C2") (pin "1") (pinfunction "1_1") (pintype "passive"))
      (node (ref "JP10") (pin "13") (pinfunction "13_13") (pintype "passive"))
      (node (ref "R5") (pin "2") (pinfunction "2_2") (pintype "passive"))
    )
    (net (code "9") (name "Net-(C2-Pad2)") (class "Default")
      (node (ref "C2") (pin "2") (pinfunction "2_2") (pintype "passive"))
      (node (ref "JP10") (pin "14") (pinfunction "14_14") (pintype "passive"))
      (node (ref "R13") (pin "1") (pinfunction "1_1") (pintype "passive"))
    )
    (net (code "10") (name "Net-(C3-Pad1)") (class "Default")
      (node (ref "C3") (pin "1") (pinfunction "1_1") (pintype "passive"))
      (node (ref "JP10") (pin "11") (pinfunction "11_11") (pintype "passive"))
      (node (ref "R4") (pin "2") (pinfunction "2_2") (pintype "passive"))
    )
    (net (code "11") (name "Net-(C3-Pad2)") (class "Default")
      (node (ref "C3") (pin "2") (pinfunction "2_2") (pintype "passive"))
      (node (ref "JP10") (pin "12") (pinfunction "12_12") (pintype "passive"))
      (node (ref "R12") (pin "1") (pinfunction "1_1") (pintype "passive"))
    )
    (net (code "12") (name "Net-(C4-Pad1)") (class "Default")
      (node (ref "C4") (pin "1") (pinfunction "1_1") (pintype "passive"))
      (node (ref "JP10") (pin "9") (pinfunction "9_9") (pintype "passive"))
      (node (ref "R3") (pin "2") (pinfunction "2_2") (pintype "passive"))
    )
    (net (code "13") (name "Net-(C4-Pad2)") (class "Default")
      (node (ref "C4") (pin "2") (pinfunction "2_2") (pintype "passive"))
      (node (ref "JP10") (pin "10") (pinfunction "10_10") (pintype "passive"))
      (node (ref "R11") (pin "1") (pinfunction "1_1") (pintype "passive"))
    )
    (net (code "14") (name "Net-(C10-Pad1)") (class "Default")
      (node (ref "C10") (pin "1") (pinfunction "1_1") (pintype "passive"))
      (node (ref "C15") (pin "1") (pinfunction "1_1") (pintype "passive"))
      (node (ref "C16") (pin "1") (pinfunction "1_1") (pintype "passive"))
      (node (ref "C9") (pin "1") (pinfunction "1_1") (pintype "passive"))
      (node (ref "F4") (pin "2A") (pinfunction "2A_2A") (pintype "passive"))
      (node (ref "F4") (pin "2B") (pinfunction "2B_2B") (pintype "passive"))
      (node (ref "U2") (pin "+VIN") (pinfunction "+VIN_+VIN") (pintype "power_in"))
    )
    (net (code "15") (name "Net-(C11-Pad1)") (class "Default")
      (node (ref "C11") (pin "1") (pinfunction "1_1") (pintype "passive"))
      (node (ref "C12") (pin "1") (pinfunction "1_1") (pintype "passive"))
      (node (ref "C5") (pin "1") (pinfunction "1_1") (pintype "passive"))
      (node (ref "C6") (pin "1") (pinfunction "1_1") (pintype "passive"))
      (node (ref "F2") (pin "2A") (pinfunction "2A_2A") (pintype "passive"))
      (node (ref "F2") (pin "2B") (pinfunction "2B_2B") (pintype "passive"))
      (node (ref "U4") (pin "+VIN") (pinfunction "+VIN_+VIN") (pintype "power_in"))
    )
    (net (code "16") (name "Net-(C13-Pad1)") (class "Default")
      (node (ref "C13") (pin "1") (pinfunction "1_1") (pintype "passive"))
      (node (ref "C14") (pin "1") (pinfunction "1_1") (pintype "passive"))
      (node (ref "C7") (pin "1") (pinfunction "1_1") (pintype "passive"))
      (node (ref "C8") (pin "1") (pinfunction "1_1") (pintype "passive"))
      (node (ref "F3") (pin "2A") (pinfunction "2A_2A") (pintype "passive"))
      (node (ref "F3") (pin "2B") (pinfunction "2B_2B") (pintype "passive"))
      (node (ref "U1") (pin "+VIN") (pinfunction "+VIN_+VIN") (pintype "power_in"))
    )
    (net (code "17") (name "Net-(D1-PadA)") (class "Default")
      (node (ref "D1") (pin "A") (pinfunction "A_A") (pintype "passive"))
      (node (ref "Q1") (pin "G") (pinfunction "G_G") (pintype "power_in"))
      (node (ref "R6") (pin "1") (pinfunction "1_1") (pintype "passive"))
    )
    (net (code "18") (name "Net-(F1-Pad1A)") (class "Default")
      (node (ref "F1") (pin "1A") (pinfunction "1A_1A") (pintype "passive"))
      (node (ref "F1") (pin "1B") (pinfunction "1B_1B") (pintype "passive"))
      (node (ref "T1") (pin "P$1") (pinfunction "P$1_P$1") (pintype "power_in"))
    )
    (net (code "19") (name "Net-(F1-Pad2A)") (class "Default")
      (node (ref "F1") (pin "2A") (pinfunction "2A_2A") (pintype "passive"))
      (node (ref "F1") (pin "2B") (pinfunction "2B_2B") (pintype "passive"))
      (node (ref "Q1") (pin "D") (pinfunction "D_D") (pintype "power_in"))
    )
    (net (code "20") (name "Net-(JP7-Pad2)") (class "Default")
      (node (ref "JP7") (pin "2") (pinfunction "2_2") (pintype "passive"))
      (node (ref "R2") (pin "2") (pinfunction "2_2") (pintype "passive"))
    )
    (net (code "21") (name "Net-(JP8-Pad1)") (class "Default")
      (node (ref "JP8") (pin "1") (pinfunction "1_1") (pintype "passive"))
      (node (ref "Q2") (pin "B") (pinfunction "B_B") (pintype "passive"))
      (node (ref "R8") (pin "2") (pinfunction "2_2") (pintype "passive"))
    )
    (net (code "22") (name "Net-(JP8-Pad2)") (class "Default")
      (node (ref "JP8") (pin "2") (pinfunction "2_2") (pintype "passive"))
      (node (ref "JP8") (pin "4") (pinfunction "4_4") (pintype "passive"))
      (node (ref "JP8") (pin "6") (pinfunction "6_6") (pintype "passive"))
      (node (ref "JP9") (pin "1") (pinfunction "1_1") (pintype "passive"))
    )
    (net (code "23") (name "Net-(JP8-Pad3)") (class "Default")
      (node (ref "JP8") (pin "3") (pinfunction "3_3") (pintype "passive"))
      (node (ref "Q3") (pin "B") (pinfunction "B_B") (pintype "passive"))
      (node (ref "R9") (pin "2") (pinfunction "2_2") (pintype "passive"))
    )
    (net (code "24") (name "Net-(JP8-Pad5)") (class "Default")
      (node (ref "JP8") (pin "5") (pinfunction "5_5") (pintype "passive"))
      (node (ref "Q4") (pin "B") (pinfunction "B_B") (pintype "passive"))
      (node (ref "R10") (pin "2") (pinfunction "2_2") (pintype "passive"))
    )
    (net (code "25") (name "Net-(LED1-PadA)") (class "Default")
      (node (ref "LED1") (pin "A") (pinfunction "A_A") (pintype "passive"))
      (node (ref "R1") (pin "1") (pinfunction "1_1") (pintype "passive"))
    )
    (net (code "26") (name "Net-(LED2-PadA)") (class "Default")
      (node (ref "LED2") (pin "A") (pinfunction "A_A") (pintype "passive"))
      (node (ref "R17") (pin "1") (pinfunction "1_1") (pintype "passive"))
    )
    (net (code "27") (name "Net-(LED3-PadA)") (class "Default")
      (node (ref "LED3") (pin "A") (pinfunction "A_A") (pintype "passive"))
      (node (ref "R18") (pin "1") (pinfunction "1_1") (pintype "passive"))
    )
    (net (code "28") (name "Net-(LED4-PadA)") (class "Default")
      (node (ref "LED4") (pin "A") (pinfunction "A_A") (pintype "passive"))
      (node (ref "R19") (pin "1") (pinfunction "1_1") (pintype "passive"))
    )
    (net (code "29") (name "Net-(Q2-PadC)") (class "Default")
      (node (ref "Q2") (pin "C") (pinfunction "C_C") (pintype "passive"))
      (node (ref "U4") (pin "RC") (pinfunction "RC_RC") (pintype "bidirectional"))
    )
    (net (code "30") (name "Net-(Q3-PadC)") (class "Default")
      (node (ref "Q3") (pin "C") (pinfunction "C_C") (pintype "passive"))
      (node (ref "U1") (pin "RC") (pinfunction "RC_RC") (pintype "bidirectional"))
    )
    (net (code "31") (name "Net-(Q4-PadC)") (class "Default")
      (node (ref "Q4") (pin "C") (pinfunction "C_C") (pintype "passive"))
      (node (ref "U2") (pin "RC") (pinfunction "RC_RC") (pintype "bidirectional"))
    )
    (net (code "32") (name "V+") (class "Default")
      (node (ref "C1") (pin "+") (pinfunction "+_+") (pintype "passive"))
      (node (ref "D1") (pin "C") (pinfunction "C_C") (pintype "passive"))
      (node (ref "F2") (pin "1A") (pinfunction "1A_1A") (pintype "passive"))
      (node (ref "F2") (pin "1B") (pinfunction "1B_1B") (pintype "passive"))
      (node (ref "F3") (pin "1A") (pinfunction "1A_1A") (pintype "passive"))
      (node (ref "F3") (pin "1B") (pinfunction "1B_1B") (pintype "passive"))
      (node (ref "F4") (pin "1A") (pinfunction "1A_1A") (pintype "passive"))
      (node (ref "F4") (pin "1B") (pinfunction "1B_1B") (pintype "passive"))
      (node (ref "Q1") (pin "S") (pinfunction "S_S") (pintype "power_in"))
      (node (ref "R1") (pin "2") (pinfunction "2_2") (pintype "passive"))
      (node (ref "R10") (pin "1") (pinfunction "1_1") (pintype "passive"))
      (node (ref "R2") (pin "1") (pinfunction "1_1") (pintype "passive"))
      (node (ref "R7") (pin "1") (pinfunction "1_1") (pintype "passive"))
      (node (ref "R8") (pin "1") (pinfunction "1_1") (pintype "passive"))
      (node (ref "R9") (pin "1") (pinfunction "1_1") (pintype "passive"))
    )
    (net (code "33") (name "V-") (class "Default")
      (node (ref "C1") (pin "-") (pinfunction "-_-") (pintype "passive"))
      (node (ref "C10") (pin "2") (pinfunction "2_2") (pintype "passive"))
      (node (ref "C11") (pin "2") (pinfunction "2_2") (pintype "passive"))
      (node (ref "C12") (pin "2") (pinfunction "2_2") (pintype "passive"))
      (node (ref "C13") (pin "2") (pinfunction "2_2") (pintype "passive"))
      (node (ref "C14") (pin "2") (pinfunction "2_2") (pintype "passive"))
      (node (ref "C15") (pin "2") (pinfunction "2_2") (pintype "passive"))
      (node (ref "C16") (pin "2") (pinfunction "2_2") (pintype "passive"))
      (node (ref "C5") (pin "2") (pinfunction "2_2") (pintype "passive"))
      (node (ref "C6") (pin "2") (pinfunction "2_2") (pintype "passive"))
      (node (ref "C7") (pin "2") (pinfunction "2_2") (pintype "passive"))
      (node (ref "C8") (pin "2") (pinfunction "2_2") (pintype "passive"))
      (node (ref "C9") (pin "2") (pinfunction "2_2") (pintype "passive"))
      (node (ref "CY1") (pin "1") (pinfunction "1_1") (pintype "passive"))
      (node (ref "CY2") (pin "1") (pinfunction "1_1") (pintype "passive"))
      (node (ref "JP7") (pin "1") (pinfunction "1_1") (pintype "passive"))
      (node (ref "JP9") (pin "2") (pinfunction "2_2") (pintype "passive"))
      (node (ref "LED1") (pin "K") (pinfunction "C_K") (pintype "passive"))
      (node (ref "Q2") (pin "E") (pinfunction "E_E") (pintype "passive"))
      (node (ref "Q3") (pin "E") (pinfunction "E_E") (pintype "passive"))
      (node (ref "Q4") (pin "E") (pinfunction "E_E") (pintype "passive"))
      (node (ref "R6") (pin "2") (pinfunction "2_2") (pintype "passive"))
      (node (ref "R7") (pin "2") (pinfunction "2_2") (pintype "passive"))
      (node (ref "T1") (pin "P$2") (pinfunction "P$2_P$2") (pintype "power_in"))
      (node (ref "U1") (pin "-VIN") (pinfunction "-VIN_-VIN") (pintype "power_in"))
      (node (ref "U2") (pin "-VIN") (pinfunction "-VIN_-VIN") (pintype "power_in"))
      (node (ref "U4") (pin "-VIN") (pinfunction "-VIN_-VIN") (pintype "power_in"))
    )
    (net (code "34") (name "unconnected-(U1-PadTRIM)") (class "Default")
      (node (ref "U1") (pin "TRIM") (pinfunction "TRIM_TRIM") (pintype "bidirectional"))
    )
    (net (code "35") (name "unconnected-(U2-PadTRIM)") (class "Default")
      (node (ref "U2") (pin "TRIM") (pinfunction "TRIM_TRIM") (pintype "bidirectional"))
    )
    (net (code "36") (name "unconnected-(U4-PadTRIM)") (class "Default")
      (node (ref "U4") (pin "TRIM") (pinfunction "TRIM_TRIM") (pintype "bidirectional"))
    )
  )
)
